# ATTINY_SERVO_BOARD.net
KiCad netlist of a schematic drawn in EAGLE
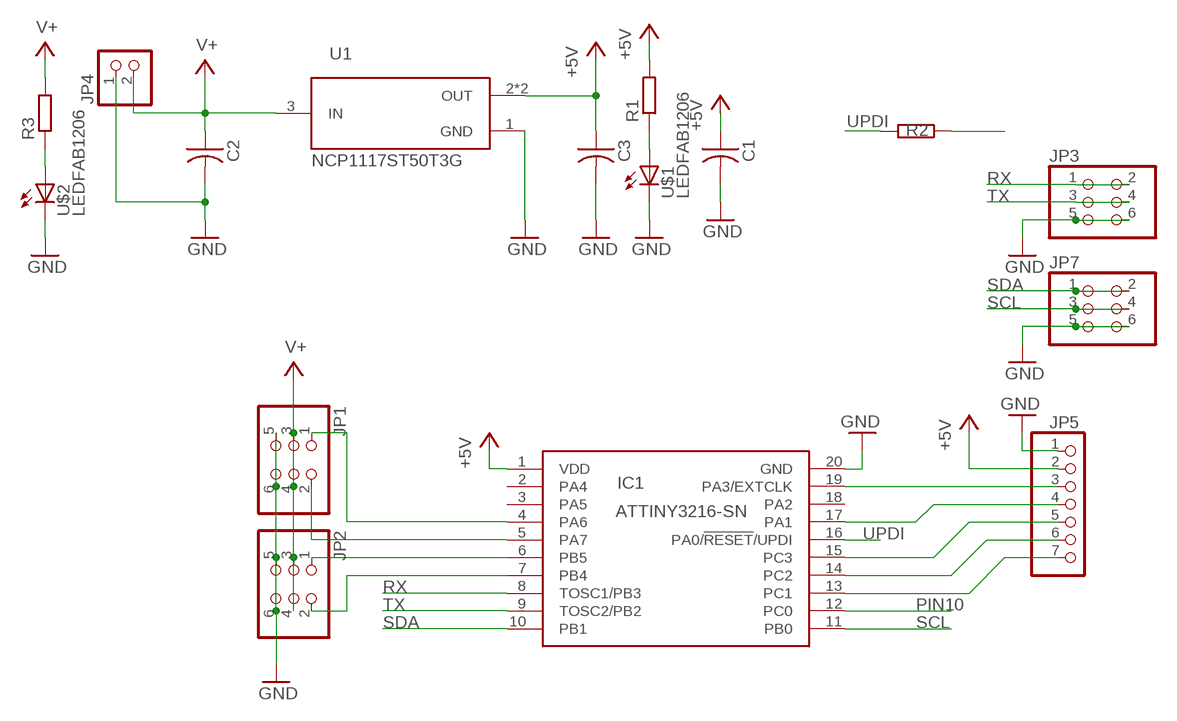
[diagram p0: schematic, sheet 1]

(export (version "E")
  (design (tool "Eeschema 10.0.6"))
  (components
    (comp (ref "C1")
      (value "CAP-US1206")
      (footprint "eagle-import:C1206")
      (libsource (lib "eagle-import") (part "CAP-US1206"))
    )
    (comp (ref "C2")
      (value "CAP-US1206")
      (footprint "eagle-import:C1206")
      (libsource (lib "eagle-import") (part "CAP-US1206"))
    )
    (comp (ref "C3")
      (value "CAP-US1206")
      (footprint "eagle-import:C1206")
      (libsource (lib "eagle-import") (part "CAP-US1206"))
    )
    (comp (ref "IC1")
      (value "ATTINY3216-SN")
      (footprint "eagle-import:SOIC127P1030X265-20N")
      (fields (field (name "MF") "Microchip Technology"))
      (libsource (lib "eagle-import") (part "ATTINY3216-SN"))
    )
    (comp (ref "JP1")
      (value "PINHD-2X03_2.54-SMD")
      (footprint "eagle-import:2X03SMD")
      (libsource (lib "eagle-import") (part "PINHD-2X03_2.54-SMD"))
    )
    (comp (ref "JP2")
      (value "PINHD-2X03_2.54-SMD")
      (footprint "eagle-import:2X03SMD")
      (libsource (lib "eagle-import") (part "PINHD-2X03_2.54-SMD"))
    )
    (comp (ref "JP3")
      (value "PINHD-2X03_2.54-SMD")
      (footprint "eagle-import:2X03SMD")
      (libsource (lib "eagle-import") (part "PINHD-2X03_2.54-SMD"))
    )
    (comp (ref "JP4")
      (value "PINHD-1X02_2.54-SMD-90°")
      (footprint "eagle-import:1X02SMD_90")
      (libsource (lib "eagle-import") (part "PINHD-1X02_2.54-SMD-90°"))
    )
    (comp (ref "JP5")
      (value "PINHD-1X07_2.54-SMD-90°")
      (footprint "eagle-import:1X07SMD_90")
      (libsource (lib "eagle-import") (part "PINHD-1X07_2.54-SMD-90°"))
    )
    (comp (ref "JP7")
      (value "PINHD-2X03_2.54-SMD")
      (footprint "eagle-import:2X03SMD")
      (libsource (lib "eagle-import") (part "PINHD-2X03_2.54-SMD"))
    )
    (comp (ref "R1")
      (value "R-EU_R1206")
      (footprint "eagle-import:R1206")
      (libsource (lib "eagle-import") (part "R-EU_R1206"))
    )
    (comp (ref "R2")
      (value "R-EU_R1206")
      (footprint "eagle-import:R1206")
      (libsource (lib "eagle-import") (part "R-EU_R1206"))
    )
    (comp (ref "R3")
      (value "R-EU_R1206")
      (footprint "eagle-import:R1206")
      (libsource (lib "eagle-import") (part "R-EU_R1206"))
    )
    (comp (ref "U$1")
      (value "LEDFAB1206")
      (footprint "eagle-import:LED1206FAB")
      (libsource (lib "eagle-import") (part "LEDFAB1206"))
    )
    (comp (ref "U$2")
      (value "LEDFAB1206")
      (footprint "eagle-import:LED1206FAB")
      (libsource (lib "eagle-import") (part "LEDFAB1206"))
    )
    (comp (ref "U1")
      (value "NCP1117ST50T3G")
      (footprint "eagle-import:SOT230P700X180-4N")
      (fields (field (name "MF") "ON Semiconductor"))
      (libsource (lib "eagle-import") (part "NCP1117ST50T3G"))
    )
  )
  (nets
    (net (code "1") (name "+5V") (class "Default")
      (node (ref "C1") (pin "1") (pinfunction "1_1") (pintype "passive"))
      (node (ref "C3") (pin "1") (pinfunction "1_1") (pintype "passive"))
      (node (ref "IC1") (pin "1") (pinfunction "VDD_1") (pintype "bidirectional"))
      (node (ref "JP5") (pin "2") (pinfunction "2_2") (pintype "passive"))
      (node (ref "R1") (pin "2") (pinfunction "2_2") (pintype "passive"))
      (node (ref "U1") (pin "2") (pinfunction "OUT_2") (pintype "output"))
      (node (ref "U1") (pin "4") (pinfunction "OUT_4") (pintype "output"))
    )
    (net (code "2") (name "/PIN10") (class "Default")
      (node (ref "IC1") (pin "12") (pinfunction "PC0_12") (pintype "bidirectional"))
    )
    (net (code "3") (name "/RX") (class "Default")
      (node (ref "IC1") (pin "8") (pinfunction "TOSC1/PB3_8") (pintype "bidirectional"))
      (node (ref "JP3") (pin "1") (pinfunction "1_1") (pintype "passive"))
      (node (ref "JP3") (pin "2") (pinfunction "2_2") (pintype "passive"))
    )
    (net (code "4") (name "/SCL") (class "Default")
      (node (ref "IC1") (pin "11") (pinfunction "PB0_11") (pintype "bidirectional"))
      (node (ref "JP7") (pin "3") (pinfunction "3_3") (pintype "passive"))
      (node (ref "JP7") (pin "4") (pinfunction "4_4") (pintype "passive"))
    )
    (net (code "5") (name "/SDA") (class "Default")
      (node (ref "IC1") (pin "10") (pinfunction "PB1_10") (pintype "bidirectional"))
      (node (ref "JP7") (pin "1") (pinfunction "1_1") (pintype "passive"))
      (node (ref "JP7") (pin "2") (pinfunction "2_2") (pintype "passive"))
    )
    (net (code "6") (name "/TX") (class "Default")
      (node (ref "IC1") (pin "9") (pinfunction "TOSC2/PB2_9") (pintype "bidirectional"))
      (node (ref "JP3") (pin "3") (pinfunction "3_3") (pintype "passive"))
      (node (ref "JP3") (pin "4") (pinfunction "4_4") (pintype "passive"))
    )
    (net (code "7") (name "/UPDI") (class "Default")
      (node (ref "IC1") (pin "16") (pinfunction "PA0/~{RESET}/UPDI_16") (pintype "bidirectional"))
      (node (ref "R2") (pin "2") (pinfunction "2_2") (pintype "passive"))
    )
    (net (code "8") (name "GND") (class "Default")
      (node (ref "C1") (pin "2") (pinfunction "2_2") (pintype "passive"))
      (node (ref "C2") (pin "2") (pinfunction "2_2") (pintype "passive"))
      (node (ref "C3") (pin "2") (pinfunction "2_2") (pintype "passive"))
      (node (ref "IC1") (pin "20") (pinfunction "GND_20") (pintype "bidirectional"))
      (node (ref "JP1") (pin "5") (pinfunction "5_5") (pintype "passive"))
      (node (ref "JP1") (pin "6") (pinfunction "6_6") (pintype "passive"))
      (node (ref "JP2") (pin "5") (pinfunction "5_5") (pintype "passive"))
      (node (ref "JP2") (pin "6") (pinfunction "6_6") (pintype "passive"))
      (node (ref "JP3") (pin "5") (pinfunction "5_5") (pintype "passive"))
      (node (ref "JP3") (pin "6") (pinfunction "6_6") (pintype "passive"))
      (node (ref "JP4") (pin "1") (pinfunction "1_1") (pintype "passive"))
      (node (ref "JP5") (pin "1") (pinfunction "1_1") (pintype "passive"))
      (node (ref "JP7") (pin "5") (pinfunction "5_5") (pintype "passive"))
      (node (ref "JP7") (pin "6") (pinfunction "6_6") (pintype "passive"))
      (node (ref "U$1") (pin "2") (pinfunction "C_2") (pintype "passive"))
      (node (ref "U$2") (pin "2") (pinfunction "C_2") (pintype "passive"))
      (node (ref "U1") (pin "1") (pinfunction "GND_1") (pintype "power_in"))
    )
    (net (code "9") (name "Net-(IC1-PA1)") (class "Default")
      (node (ref "IC1") (pin "17") (pinfunction "PA1_17") (pintype "bidirectional"))
      (node (ref "JP5") (pin "4") (pinfunction "4_4") (pintype "passive"))
    )
    (net (code "10") (name "Net-(IC1-PA3{slash}EXTCLK)") (class "Default")
      (node (ref "IC1") (pin "19") (pinfunction "PA3/EXTCLK_19") (pintype "bidirectional"))
      (node (ref "JP5") (pin "3") (pinfunction "3_3") (pintype "passive"))
    )
    (net (code "11") (name "Net-(IC1-PA6)") (class "Default")
      (node (ref "IC1") (pin "4") (pinfunction "PA6_4") (pintype "bidirectional"))
      (node (ref "JP1") (pin "1") (pinfunction "1_1") (pintype "passive"))
    )
    (net (code "12") (name "Net-(IC1-PA7)") (class "Default")
      (node (ref "IC1") (pin "5") (pinfunction "PA7_5") (pintype "bidirectional"))
      (node (ref "JP1") (pin "2") (pinfunction "2_2") (pintype "passive"))
    )
    (net (code "13") (name "Net-(IC1-PB4)") (class "Default")
      (node (ref "IC1") (pin "7") (pinfunction "PB4_7") (pintype "bidirectional"))
      (node (ref "JP2") (pin "2") (pinfunction "2_2") (pintype "passive"))
    )
    (net (code "14") (name "Net-(IC1-PB5)") (class "Default")
      (node (ref "IC1") (pin "6") (pinfunction "PB5_6") (pintype "bidirectional"))
      (node (ref "JP2") (pin "1") (pinfunction "1_1") (pintype "passive"))
    )
    (net (code "15") (name "Net-(IC1-PC1)") (class "Default")
      (node (ref "IC1") (pin "13") (pinfunction "PC1_13") (pintype "bidirectional"))
      (node (ref "JP5") (pin "7") (pinfunction "7_7") (pintype "passive"))
    )
    (net (code "16") (name "Net-(IC1-PC2)") (class "Default")
      (node (ref "IC1") (pin "14") (pinfunction "PC2_14") (pintype "bidirectional"))
      (node (ref "JP5") (pin "6") (pinfunction "6_6") (pintype "passive"))
    )
    (net (code "17") (name "Net-(IC1-PC3)") (class "Default")
      (node (ref "IC1") (pin "15") (pinfunction "PC3_15") (pintype "bidirectional"))
      (node (ref "JP5") (pin "5") (pinfunction "5_5") (pintype "passive"))
    )
    (net (code "18") (name "Net-(U$1-A)") (class "Default")
      (node (ref "R1") (pin "1") (pinfunction "1_1") (pintype "passive"))
      (node (ref "U$1") (pin "1") (pinfunction "A_1") (pintype "passive"))
    )
    (net (code "19") (name "Net-(U$2-A)") (class "Default")
      (node (ref "R3") (pin "1") (pinfunction "1_1") (pintype "passive"))
      (node (ref "U$2") (pin "1") (pinfunction "A_1") (pintype "passive"))
    )
    (net (code "20") (name "V+") (class "Default")
      (node (ref "C2") (pin "1") (pinfunction "1_1") (pintype "passive"))
      (node (ref "JP1") (pin "3") (pinfunction "3_3") (pintype "passive"))
      (node (ref "JP1") (pin "4") (pinfunction "4_4") (pintype "passive"))
      (node (ref "JP2") (pin "3") (pinfunction "3_3") (pintype "passive"))
      (node (ref "JP2") (pin "4") (pinfunction "4_4") (pintype "passive"))
      (node (ref "JP4") (pin "2") (pinfunction "2_2") (pintype "passive"))
      (node (ref "R3") (pin "2") (pinfunction "2_2") (pintype "passive"))
      (node (ref "U1") (pin "3") (pinfunction "IN_3") (pintype "input"))
    )
    (net (code "21") (name "unconnected-(IC1-PA2-Pad18)") (class "Default")
      (node (ref "IC1") (pin "18") (pinfunction "PA2_18") (pintype "bidirectional"))
    )
    (net (code "22") (name "unconnected-(IC1-PA4-Pad2)") (class "Default")
      (node (ref "IC1") (pin "2") (pinfunction "PA4_2") (pintype "bidirectional"))
    )
    (net (code "23") (name "unconnected-(IC1-PA5-Pad3)") (class "Default")
      (node (ref "IC1") (pin "3") (pinfunction "PA5_3") (pintype "bidirectional"))
    )
    (net (code "24") (name "unconnected-(R2-Pad1)") (class "Default")
      (node (ref "R2") (pin "1") (pinfunction "1_1") (pintype "passive"))
    )
  )
)
